# RadTherm.net
KiCad netlist of a schematic drawn in EAGLE
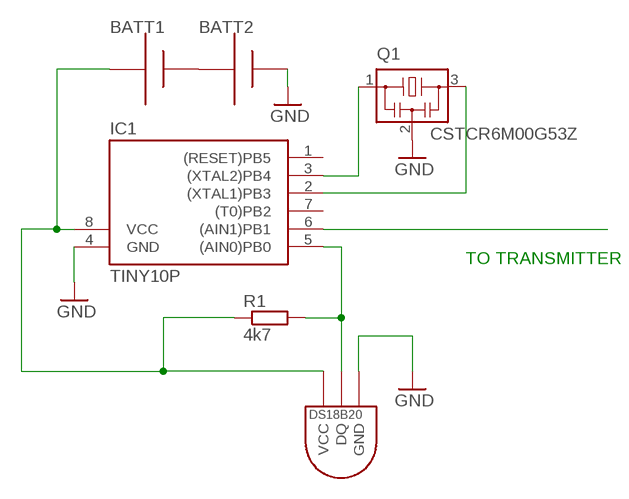
[diagram p0: schematic, sheet 1]

(export (version "E")
  (design (tool "Eeschema 10.0.6"))
  (components
    (comp (ref "BATT1")
      (value "AAA")
      (footprint "eagle-import:12BH412")
      (libsource (lib "eagle-import") (part "AAA"))
    )
    (comp (ref "BATT2")
      (value "AAA")
      (footprint "eagle-import:12BH412")
      (libsource (lib "eagle-import") (part "AAA"))
    )
    (comp (ref "IC1")
      (value "TINY10P")
      (footprint "eagle-import:DIL08")
      (libsource (lib "eagle-import") (part "TINY10P"))
    )
    (comp (ref "Q1")
      (value "CSTCR6M00G53Z")
      (footprint "eagle-import:CSTCR6M")
      (fields (field (name "MPN") "CSTCR6M00G53-R0"))
      (libsource (lib "eagle-import") (part "CSTCR6M00G53Z"))
    )
    (comp (ref "R1")
      (value "4k7")
      (footprint "eagle-import:0204_7")
      (libsource (lib "eagle-import") (part "R-EU_0204/7"))
    )
    (comp (ref "U$1")
      (value "DS1820TO92")
      (footprint "eagle-import:DS1820")
      (libsource (lib "eagle-import") (part "DS1820TO92"))
    )
  )
  (nets
    (net (code "1") (name "GND") (class "Default")
      (node (ref "BATT2") (pin "+") (pinfunction "+_+") (pintype "bidirectional"))
      (node (ref "IC1") (pin "4") (pinfunction "GND_4") (pintype "power_in"))
      (node (ref "Q1") (pin "2") (pinfunction "2_2") (pintype "passive"))
      (node (ref "U$1") (pin "GND") (pinfunction "GND_GND") (pintype "power_in"))
    )
    (net (code "2") (name "Net-(BATT1-Pad+)") (class "Default")
      (node (ref "BATT1") (pin "+") (pinfunction "+_+") (pintype "bidirectional"))
      (node (ref "BATT2") (pin "-") (pinfunction "-_-") (pintype "bidirectional"))
    )
    (net (code "3") (name "Net-(IC1-(AIN0)PB0)") (class "Default")
      (node (ref "IC1") (pin "5") (pinfunction "(AIN0)PB0_5") (pintype "bidirectional"))
      (node (ref "R1") (pin "2") (pinfunction "2_2") (pintype "passive"))
      (node (ref "U$1") (pin "DQ") (pinfunction "DQ_DQ") (pintype "bidirectional"))
    )
    (net (code "4") (name "Net-(IC1-(XTAL1)PB3)") (class "Default")
      (node (ref "IC1") (pin "2") (pinfunction "(XTAL1)PB3_2") (pintype "bidirectional"))
      (node (ref "Q1") (pin "3") (pinfunction "3_3") (pintype "passive"))
    )
    (net (code "5") (name "Net-(IC1-(XTAL2)PB4)") (class "Default")
      (node (ref "IC1") (pin "3") (pinfunction "(XTAL2)PB4_3") (pintype "bidirectional"))
      (node (ref "Q1") (pin "1") (pinfunction "1_1") (pintype "passive"))
    )
    (net (code "6") (name "Net-(IC1-VCC)") (class "Default")
      (node (ref "BATT1") (pin "-") (pinfunction "-_-") (pintype "bidirectional"))
      (node (ref "IC1") (pin "8") (pinfunction "VCC_8") (pintype "power_in"))
      (node (ref "R1") (pin "1") (pinfunction "1_1") (pintype "passive"))
      (node (ref "U$1") (pin "VDD") (pinfunction "VCC_VDD") (pintype "power_in"))
    )
    (net (code "7") (name "unconnected-(IC1-(AIN1)PB1-Pad6)") (class "Default")
      (node (ref "IC1") (pin "6") (pinfunction "(AIN1)PB1_6") (pintype "bidirectional"))
    )
    (net (code "8") (name "unconnected-(IC1-(RESET)PB5-Pad1)") (class "Default")
      (node (ref "IC1") (pin "1") (pinfunction "(RESET)PB5_1") (pintype "bidirectional"))
    )
    (net (code "9") (name "unconnected-(IC1-(T0)PB2-Pad7)") (class "Default")
      (node (ref "IC1") (pin "7") (pinfunction "(T0)PB2_7") (pintype "bidirectional"))
    )
  )
)
